# vlc_ctrl_T67.net
KiCad netlist of a schematic drawn in Altium Designer
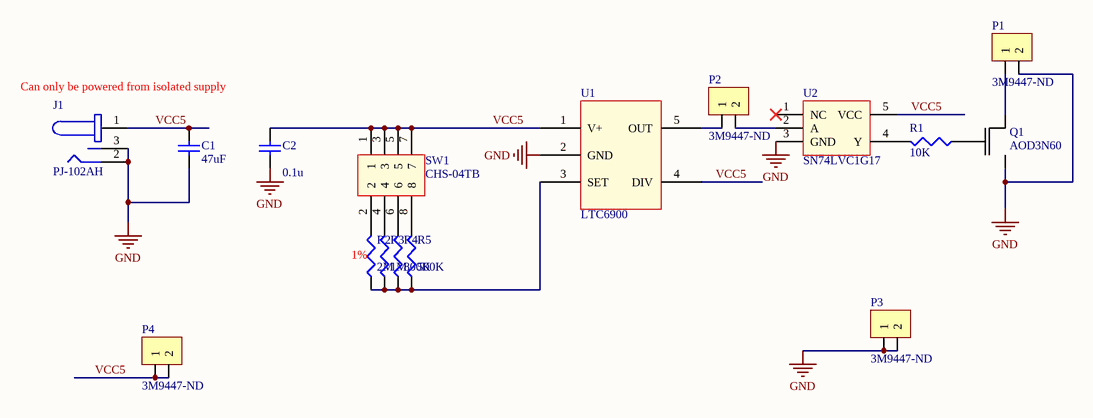
[diagram p0: vlc_ctrl_T67.SchDoc]

(export (version "E")
  (design (tool "Eeschema 10.0.6"))
  (components
    (comp (ref "C1")
      (value "47uF")
      (footprint "C1210")
      (description "Capacitor (Semiconductor SIM Model)")
      (fields (field (name "Comment") "Cap Semi") (field (name "PUBLISHER") "Altium Limited"))
      (libsource (lib "Miscellaneous Devices") (part "Cap Semi"))
    )
    (comp (ref "C2")
      (value "0.1u")
      (footprint "1608[0603]")
      (description "Capacitor (Semiconductor SIM Model)")
      (fields (field (name "Comment") "Cap Semi") (field (name "PUBLISHER") "Altium Limited"))
      (libsource (lib "Miscellaneous Devices") (part "Cap Semi"))
    )
    (comp (ref "J1")
      (value "PJ-102AH")
      (footprint "PJ-102AH")
      (description "CONN PWR JACK 2.1X5.5MM HIGH CUR")
      (libsource (lib "vlc_ctrl") (part "PJ-102AH"))
    )
    (comp (ref "P1")
      (value "1 x 2 header")
      (footprint "1x2 header")
      (description "100 mils standard header")
      (fields (field (name "SUPPLIER PART NUMBER 1") "3M9447-ND"))
      (libsource (lib "vlc_ctrl") (part "1 x 2 header"))
    )
    (comp (ref "P2")
      (value "1 x 2 header")
      (footprint "1x2 header")
      (description "100 mils standard header")
      (fields (field (name "SUPPLIER PART NUMBER 1") "3M9447-ND"))
      (libsource (lib "vlc_ctrl") (part "1 x 2 header"))
    )
    (comp (ref "P3")
      (value "1 x 2 header")
      (footprint "1x2 header")
      (description "100 mils standard header")
      (fields (field (name "SUPPLIER PART NUMBER 1") "3M9447-ND"))
      (libsource (lib "vlc_ctrl") (part "1 x 2 header"))
    )
    (comp (ref "P4")
      (value "1 x 2 header")
      (footprint "1x2 header")
      (description "100 mils standard header")
      (fields (field (name "SUPPLIER PART NUMBER 1") "3M9447-ND"))
      (libsource (lib "vlc_ctrl") (part "1 x 2 header"))
    )
    (comp (ref "Q1")
      (value "AOD3N60")
      (footprint "TO252")
      (description "600V,2.5A N-Channel MOSFET")
      (libsource (lib "vlc_ctrl") (part "AOD3N60"))
    )
    (comp (ref "R1")
      (value "10K")
      (footprint "J1-0603")
      (description "Resistor")
      (fields (field (name "Comment") "Res3") (field (name "PUBLISHER") "Altium Limited"))
      (libsource (lib "Miscellaneous Devices") (part "Res3"))
    )
    (comp (ref "R2")
      (value "2M")
      (footprint "J1-0603")
      (description "Resistor")
      (fields (field (name "Comment") "Res3") (field (name "PUBLISHER") "Altium Limited"))
      (libsource (lib "Miscellaneous Devices") (part "Res3"))
    )
    (comp (ref "R3")
      (value "1M")
      (footprint "J1-0603")
      (description "Resistor")
      (fields (field (name "Comment") "Res3") (field (name "PUBLISHER") "Altium Limited"))
      (libsource (lib "Miscellaneous Devices") (part "Res3"))
    )
    (comp (ref "R4")
      (value "800K")
      (footprint "J1-0603")
      (description "Resistor")
      (fields (field (name "Comment") "Res3") (field (name "PUBLISHER") "Altium Limited"))
      (libsource (lib "Miscellaneous Devices") (part "Res3"))
    )
    (comp (ref "R5")
      (value "500K")
      (footprint "J1-0603")
      (description "Resistor")
      (fields (field (name "Comment") "Res3") (field (name "PUBLISHER") "Altium Limited"))
      (libsource (lib "Miscellaneous Devices") (part "Res3"))
    )
    (comp (ref "SW1")
      (value "CHS-04TB")
      (footprint "CHS04TB")
      (description "SLIDE SWITCHES")
      (libsource (lib "vlc_ctrl") (part "CHS-04TB"))
    )
    (comp (ref "U1")
      (value "LTC6900")
      (footprint "TSOT23")
      (description "Low Power, 1kHz to 20MHz   Resistor Set SOT-23 Oscillator")
      (libsource (lib "vlc_ctrl") (part "LTC6900"))
    )
    (comp (ref "U2")
      (value "SN74LVC1G17")
      (footprint "SOT23-5")
      (description "SINGLE SCHMITT-TRIGGER BUFFER")
      (libsource (lib "vlc_ctrl") (part "SN74LVC1G17"))
    )
  )
  (nets
    (net (code "1") (name "/VCC5") (class "Default")
      (node (ref "C1") (pin "2") (pinfunction "2_2") (pintype "passive"))
      (node (ref "C2") (pin "2") (pinfunction "2_2") (pintype "passive"))
      (node (ref "J1") (pin "1") (pintype "passive"))
      (node (ref "P4") (pin "1") (pinfunction "1_1") (pintype "passive"))
      (node (ref "P4") (pin "2") (pinfunction "2_2") (pintype "passive"))
      (node (ref "SW1") (pin "1") (pinfunction "1_1") (pintype "passive"))
      (node (ref "SW1") (pin "3") (pinfunction "3_3") (pintype "passive"))
      (node (ref "SW1") (pin "5") (pinfunction "5_5") (pintype "passive"))
      (node (ref "SW1") (pin "7") (pinfunction "7_7") (pintype "passive"))
      (node (ref "U1") (pin "1") (pinfunction "V+_1") (pintype "passive"))
      (node (ref "U1") (pin "4") (pinfunction "DIV_4") (pintype "passive"))
      (node (ref "U2") (pin "5") (pinfunction "VCC_5") (pintype "passive"))
    )
    (net (code "2") (name "GND") (class "Default")
      (node (ref "C1") (pin "1") (pinfunction "1_1") (pintype "passive"))
      (node (ref "C2") (pin "1") (pinfunction "1_1") (pintype "passive"))
      (node (ref "J1") (pin "2") (pintype "passive"))
      (node (ref "J1") (pin "3") (pintype "passive"))
      (node (ref "P1") (pin "2") (pinfunction "2_2") (pintype "passive"))
      (node (ref "P3") (pin "1") (pinfunction "1_1") (pintype "passive"))
      (node (ref "P3") (pin "2") (pinfunction "2_2") (pintype "passive"))
      (node (ref "Q1") (pin "3") (pinfunction "S_3") (pintype "passive"))
      (node (ref "U1") (pin "2") (pinfunction "GND_2") (pintype "passive"))
      (node (ref "U2") (pin "3") (pinfunction "GND_3") (pintype "passive"))
    )
    (net (code "3") (name "Net-(Q1-D)") (class "Default")
      (node (ref "P1") (pin "1") (pinfunction "1_1") (pintype "passive"))
      (node (ref "Q1") (pin "4") (pinfunction "D_4") (pintype "passive"))
    )
    (net (code "4") (name "Net-(Q1-G)") (class "Default")
      (node (ref "Q1") (pin "1") (pinfunction "G_1") (pintype "passive"))
      (node (ref "R1") (pin "1") (pinfunction "1_1") (pintype "passive"))
    )
    (net (code "5") (name "Net-(R2-Pad2)") (class "Default")
      (node (ref "R2") (pin "2") (pinfunction "2_2") (pintype "passive"))
      (node (ref "SW1") (pin "2") (pinfunction "2_2") (pintype "passive"))
    )
    (net (code "6") (name "Net-(R3-Pad2)") (class "Default")
      (node (ref "R3") (pin "2") (pinfunction "2_2") (pintype "passive"))
      (node (ref "SW1") (pin "4") (pinfunction "4_4") (pintype "passive"))
    )
    (net (code "7") (name "Net-(R4-Pad2)") (class "Default")
      (node (ref "R4") (pin "2") (pinfunction "2_2") (pintype "passive"))
      (node (ref "SW1") (pin "6") (pinfunction "6_6") (pintype "passive"))
    )
    (net (code "8") (name "Net-(R5-Pad2)") (class "Default")
      (node (ref "R5") (pin "2") (pinfunction "2_2") (pintype "passive"))
      (node (ref "SW1") (pin "8") (pinfunction "8_8") (pintype "passive"))
    )
    (net (code "9") (name "Net-(U1-OUT)") (class "Default")
      (node (ref "P2") (pin "1") (pinfunction "1_1") (pintype "passive"))
      (node (ref "U1") (pin "5") (pinfunction "OUT_5") (pintype "passive"))
    )
    (net (code "10") (name "Net-(U1-SET)") (class "Default")
      (node (ref "R2") (pin "1") (pinfunction "1_1") (pintype "passive"))
      (node (ref "R3") (pin "1") (pinfunction "1_1") (pintype "passive"))
      (node (ref "R4") (pin "1") (pinfunction "1_1") (pintype "passive"))
      (node (ref "R5") (pin "1") (pinfunction "1_1") (pintype "passive"))
      (node (ref "U1") (pin "3") (pinfunction "SET_3") (pintype "passive"))
    )
    (net (code "11") (name "Net-(U2-A)") (class "Default")
      (node (ref "P2") (pin "2") (pinfunction "2_2") (pintype "passive"))
      (node (ref "U2") (pin "2") (pinfunction "A_2") (pintype "passive"))
    )
    (net (code "12") (name "Net-(U2-Y)") (class "Default")
      (node (ref "R1") (pin "2") (pinfunction "2_2") (pintype "passive"))
      (node (ref "U2") (pin "4") (pinfunction "Y_4") (pintype "passive"))
    )
    (net (code "13") (name "unconnected-(U2-NC-Pad1)") (class "Default")
      (node (ref "U2") (pin "1") (pinfunction "NC_1") (pintype "passive+no_connect"))
    )
  )
)
